# SCH_555-circuit_2025-03-24.net
KiCad netlist of a schematic drawn in EasyEDA
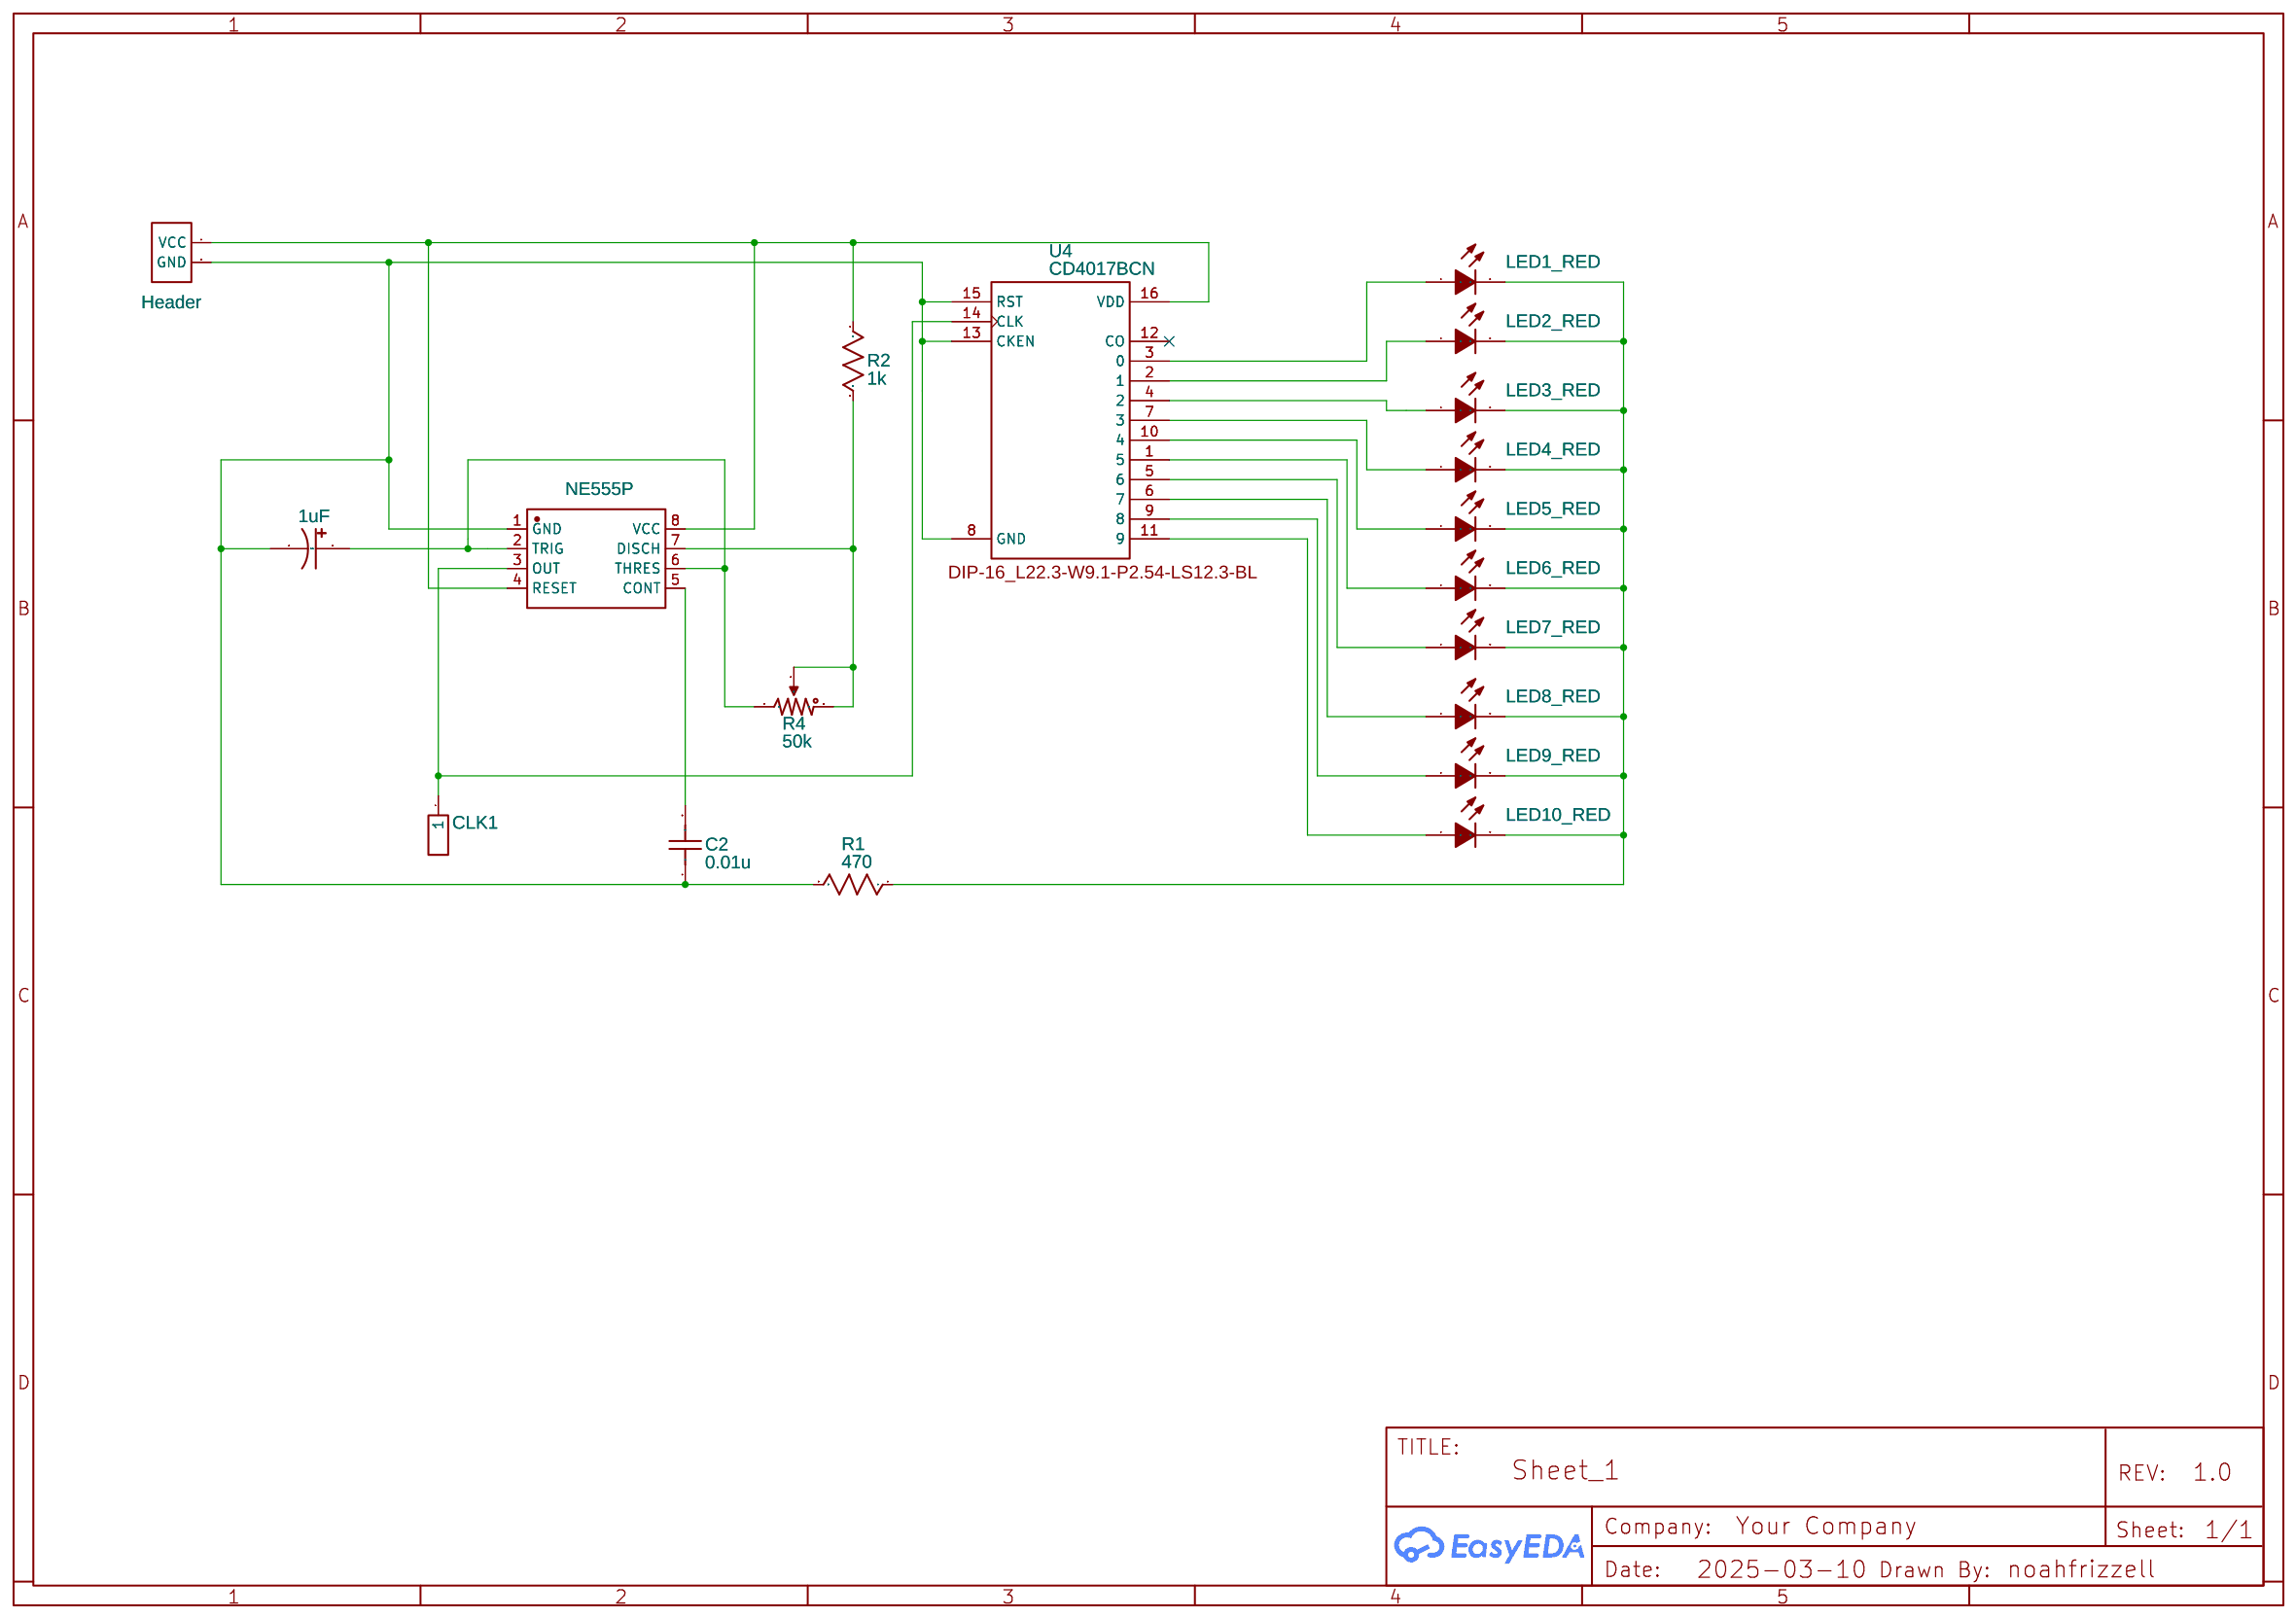
[diagram p0: schematic sheet]

(export (version "E")
  (design (tool "Eeschema 10.0.6"))
  (components
    (comp (ref "C1")
      (value "1uF")
      (fields (field (name "Manufacturer Part") "UVZ1H010MDD") (field (name "Manufacturer") "Nichicon(尼吉康)"))
      (libsource (lib "") (part "UVZ1H010MDD"))
    )
    (comp (ref "C2") (value "0.01u") (libsource (lib "") (part "C_0603_US")))
    (comp (ref "CLK1")
      (value "C81276")
      (fields
        (field (name "Manufacturer Part") "2.54-1*1P针")
        (field (name "Manufacturer") "BOOMELE(Boom Precision Elec)")
      )
      (libsource (lib "") (part "Header-Male-2.54_1x1"))
    )
    (comp (ref "H1") (value "Header") (libsource (lib "") (part "HEADER-FEMALE-2.54_1X2")))
    (comp (ref "LED1_RED") (value "LED_5MM") (libsource (lib "") (part "LED_5MM_6")))
    (comp (ref "LED2_RED") (value "LED_5MM") (libsource (lib "") (part "LED_5MM_9")))
    (comp (ref "LED3_RED") (value "LED_5MM") (libsource (lib "") (part "LED_5MM_5")))
    (comp (ref "LED4_RED") (value "LED_5MM") (libsource (lib "") (part "LED_5MM_8")))
    (comp (ref "LED5_RED") (value "LED_5MM") (libsource (lib "") (part "LED_5MM")))
    (comp (ref "LED6_RED") (value "LED_5MM") (libsource (lib "") (part "LED_5MM_3")))
    (comp (ref "LED7_RED") (value "LED_5MM") (libsource (lib "") (part "LED_5MM_2")))
    (comp (ref "LED8_RED") (value "LED_5MM") (libsource (lib "") (part "LED_5MM_4")))
    (comp (ref "LED9_RED") (value "LED_5MM") (libsource (lib "") (part "LED_5MM_7")))
    (comp (ref "LED10_RED") (value "LED_5MM") (libsource (lib "") (part "LED_5MM_1")))
    (comp (ref "R1")
      (value "470")
      (fields (field (name "Manufacturer Part") "?"))
      (libsource (lib "") (part "Resistor_1"))
    )
    (comp (ref "R2")
      (value "1k")
      (fields (field (name "Manufacturer Part") "?"))
      (libsource (lib "") (part "Resistor"))
    )
    (comp (ref "R4")
      (value "50k")
      (fields (field (name "Manufacturer Part") "?"))
      (libsource (lib "") (part "Potentiometer"))
    )
    (comp (ref "U2")
      (value "NE555P")
      (fields (field (name "Manufacturer") "TI(德州仪器)"))
      (libsource (lib "") (part "NE555P"))
    )
    (comp (ref "U4") (value "CD4017BCN") (libsource (lib "") (part "CD4017BCN")))
  )
  (nets
    (net (code "1") (name "Net-(H1-GND)") (class "Default")
      (node (ref "C1") (pin "2") (pinfunction "2_2") (pintype "unspecified"))
      (node (ref "C2") (pin "1") (pinfunction "1_1") (pintype "unspecified"))
      (node (ref "H1") (pin "2") (pinfunction "GND_2") (pintype "unspecified"))
      (node (ref "R1") (pin "2") (pinfunction "2_2") (pintype "unspecified"))
      (node (ref "U2") (pin "1") (pinfunction "GND_1") (pintype "unspecified"))
      (node (ref "U4") (pin "13") (pinfunction "CKEN_13") (pintype "unspecified"))
      (node (ref "U4") (pin "15") (pinfunction "RST_15") (pintype "unspecified"))
      (node (ref "U4") (pin "8") (pinfunction "GND_8") (pintype "passive"))
    )
    (net (code "2") (name "Net-(H1-VCC)") (class "Default")
      (node (ref "H1") (pin "1") (pinfunction "VCC_1") (pintype "unspecified"))
      (node (ref "R2") (pin "1") (pinfunction "1_1") (pintype "unspecified"))
      (node (ref "U2") (pin "4") (pinfunction "RESET_4") (pintype "unspecified"))
      (node (ref "U2") (pin "8") (pinfunction "VCC_8") (pintype "unspecified"))
      (node (ref "U4") (pin "16") (pinfunction "VDD_16") (pintype "passive"))
    )
    (net (code "3") (name "Net-(LED1_RED-A)") (class "Default")
      (node (ref "LED1_RED") (pin "1") (pinfunction "A_1") (pintype "input"))
      (node (ref "U4") (pin "3") (pinfunction "0_3") (pintype "output"))
    )
    (net (code "4") (name "Net-(LED2_RED-A)") (class "Default")
      (node (ref "LED2_RED") (pin "1") (pinfunction "A_1") (pintype "input"))
      (node (ref "U4") (pin "2") (pinfunction "1_2") (pintype "output"))
    )
    (net (code "5") (name "Net-(LED3_RED-A)") (class "Default")
      (node (ref "LED3_RED") (pin "1") (pinfunction "A_1") (pintype "input"))
      (node (ref "U4") (pin "4") (pinfunction "2_4") (pintype "output"))
    )
    (net (code "6") (name "Net-(LED4_RED-A)") (class "Default")
      (node (ref "LED4_RED") (pin "1") (pinfunction "A_1") (pintype "input"))
      (node (ref "U4") (pin "7") (pinfunction "3_7") (pintype "output"))
    )
    (net (code "7") (name "Net-(LED5_RED-A)") (class "Default")
      (node (ref "LED5_RED") (pin "1") (pinfunction "A_1") (pintype "input"))
      (node (ref "U4") (pin "10") (pinfunction "4_10") (pintype "output"))
    )
    (net (code "8") (name "Net-(LED6_RED-A)") (class "Default")
      (node (ref "LED6_RED") (pin "1") (pinfunction "A_1") (pintype "input"))
      (node (ref "U4") (pin "1") (pinfunction "5_1") (pintype "output"))
    )
    (net (code "9") (name "Net-(LED7_RED-A)") (class "Default")
      (node (ref "LED7_RED") (pin "1") (pinfunction "A_1") (pintype "input"))
      (node (ref "U4") (pin "5") (pinfunction "6_5") (pintype "output"))
    )
    (net (code "10") (name "Net-(LED8_RED-A)") (class "Default")
      (node (ref "LED8_RED") (pin "1") (pinfunction "A_1") (pintype "input"))
      (node (ref "U4") (pin "6") (pinfunction "7_6") (pintype "output"))
    )
    (net (code "11") (name "Net-(LED9_RED-A)") (class "Default")
      (node (ref "LED9_RED") (pin "1") (pinfunction "A_1") (pintype "input"))
      (node (ref "U4") (pin "9") (pinfunction "8_9") (pintype "output"))
    )
    (net (code "12") (name "Net-(LED10_RED-A)") (class "Default")
      (node (ref "LED10_RED") (pin "1") (pinfunction "A_1") (pintype "input"))
      (node (ref "U4") (pin "11") (pinfunction "9_11") (pintype "output"))
    )
    (net (code "13") (name "Net-(LED10_RED-K)") (class "Default")
      (node (ref "LED10_RED") (pin "2") (pinfunction "K_2") (pintype "input"))
      (node (ref "LED1_RED") (pin "2") (pinfunction "K_2") (pintype "input"))
      (node (ref "LED2_RED") (pin "2") (pinfunction "K_2") (pintype "input"))
      (node (ref "LED3_RED") (pin "2") (pinfunction "K_2") (pintype "input"))
      (node (ref "LED4_RED") (pin "2") (pinfunction "K_2") (pintype "input"))
      (node (ref "LED5_RED") (pin "2") (pinfunction "K_2") (pintype "input"))
      (node (ref "LED6_RED") (pin "2") (pinfunction "K_2") (pintype "input"))
      (node (ref "LED7_RED") (pin "2") (pinfunction "K_2") (pintype "input"))
      (node (ref "LED8_RED") (pin "2") (pinfunction "K_2") (pintype "input"))
      (node (ref "LED9_RED") (pin "2") (pinfunction "K_2") (pintype "input"))
      (node (ref "R1") (pin "1") (pinfunction "1_1") (pintype "unspecified"))
    )
    (net (code "14") (name "Net-(R4-2)") (class "Default")
      (node (ref "R2") (pin "2") (pinfunction "2_2") (pintype "unspecified"))
      (node (ref "R4") (pin "2") (pinfunction "3_2") (pintype "unspecified"))
      (node (ref "R4") (pin "3") (pinfunction "2_3") (pintype "unspecified"))
      (node (ref "U2") (pin "7") (pinfunction "DISCH_7") (pintype "unspecified"))
    )
    (net (code "15") (name "Net-(U2-CONT)") (class "Default")
      (node (ref "C2") (pin "2") (pinfunction "2_2") (pintype "unspecified"))
      (node (ref "U2") (pin "5") (pinfunction "CONT_5") (pintype "unspecified"))
    )
    (net (code "16") (name "Net-(U2-OUT)") (class "Default")
      (node (ref "CLK1") (pin "1") (pinfunction "1_1") (pintype "unspecified"))
      (node (ref "U2") (pin "3") (pinfunction "OUT_3") (pintype "unspecified"))
      (node (ref "U4") (pin "14") (pinfunction "CLK_14") (pintype "unspecified"))
    )
    (net (code "17") (name "Net-(U2-THRES)") (class "Default")
      (node (ref "C1") (pin "1") (pinfunction "1_1") (pintype "unspecified"))
      (node (ref "R4") (pin "1") (pinfunction "1_1") (pintype "unspecified"))
      (node (ref "U2") (pin "2") (pinfunction "TRIG_2") (pintype "unspecified"))
      (node (ref "U2") (pin "6") (pinfunction "THRES_6") (pintype "unspecified"))
    )
    (net (code "18") (name "unconnected-(U4-CO-Pad12)") (class "Default")
      (node (ref "U4") (pin "12") (pinfunction "CO_12") (pintype "output+no_connect"))
    )
  )
)
